# pcb.net
KiCad netlist of a schematic drawn in EAGLE
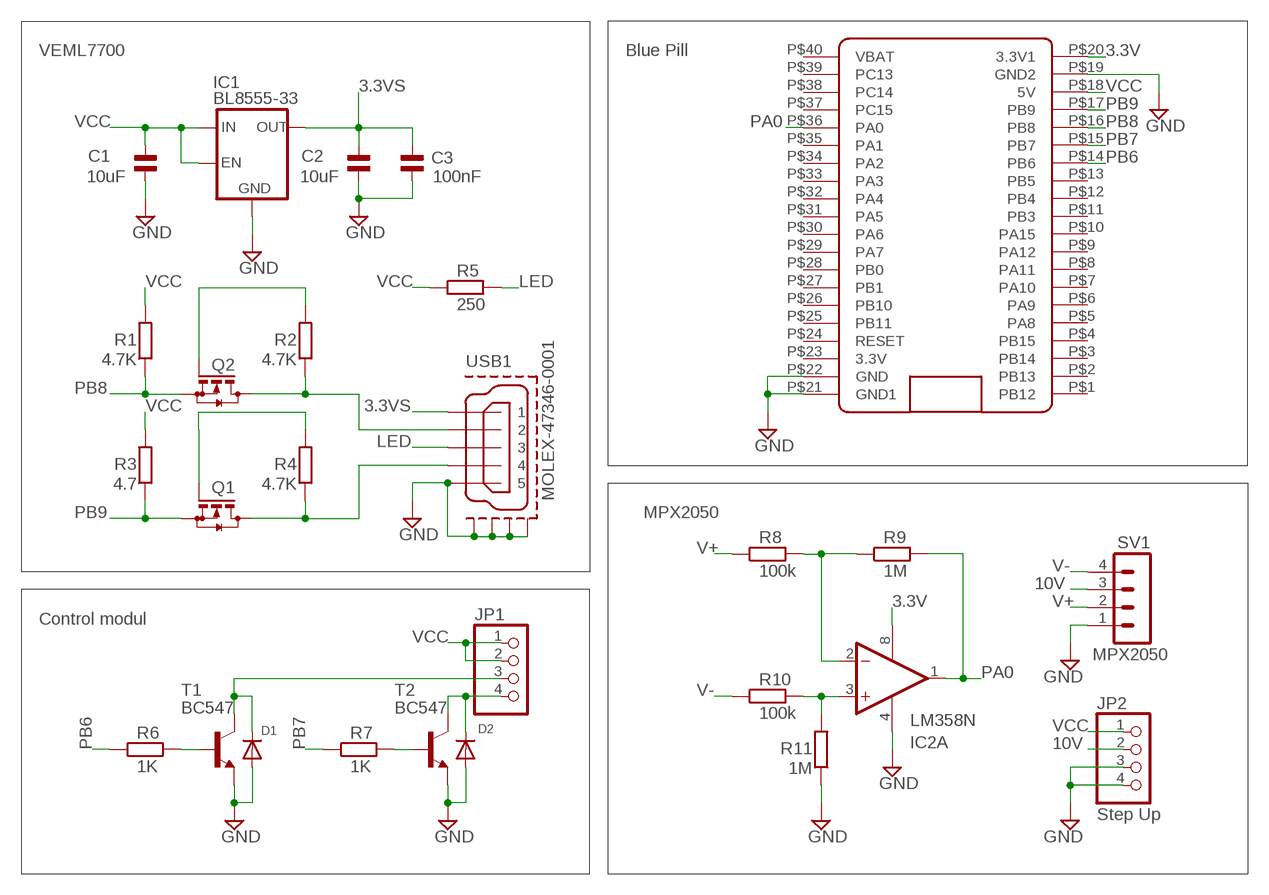
[diagram p0: schematic, sheet 1]

(export (version "E")
  (design (tool "Eeschema 10.0.6"))
  (components
    (comp (ref "C1")
      (value "10uF")
      (footprint "eagle-import:C-0805")
      (libsource (lib "eagle-import") (part "C-NP-SMD-0805"))
    )
    (comp (ref "C2")
      (value "10uF")
      (footprint "eagle-import:C-0805")
      (libsource (lib "eagle-import") (part "C-NP-SMD-0805"))
    )
    (comp (ref "C3")
      (value "100nF")
      (footprint "eagle-import:C-0805")
      (libsource (lib "eagle-import") (part "C-NP-SMD-0805"))
    )
    (comp (ref "D1")
      (value "DIODESOD-123")
      (footprint "eagle-import:SOD-123")
      (libsource (lib "eagle-import") (part "DIODESOD-123"))
    )
    (comp (ref "D2")
      (value "DIODESOD-123")
      (footprint "eagle-import:SOD-123")
      (libsource (lib "eagle-import") (part "DIODESOD-123"))
    )
    (comp (ref "IC1")
      (value "BL8555-33")
      (footprint "eagle-import:SOT23-5")
      (fields (field (name "MF") "Texas Instruments") (field (name "MPN") "TPS70928DBVT"))
      (libsource (lib "eagle-import") (part "TPS709DBV28"))
    )
    (comp (ref "IC2")
      (value "LM358N")
      (footprint "eagle-import:DIL08")
      (libsource (lib "eagle-import") (part "LM358N"))
    )
    (comp (ref "JP1")
      (value "PINHD-1X4")
      (footprint "eagle-import:1X04")
      (libsource (lib "eagle-import") (part "PINHD-1X4"))
    )
    (comp (ref "JP2")
      (value "Step Up")
      (footprint "eagle-import:1X04")
      (libsource (lib "eagle-import") (part "PINHD-1X4"))
    )
    (comp (ref "Q1")
      (value "BSS123")
      (footprint "eagle-import:SOT23")
      (libsource (lib "eagle-import") (part "BSS123"))
    )
    (comp (ref "Q2")
      (value "BSS123")
      (footprint "eagle-import:SOT23")
      (libsource (lib "eagle-import") (part "BSS123"))
    )
    (comp (ref "R1")
      (value "4.7K")
      (footprint "eagle-import:M0805")
      (libsource (lib "eagle-import") (part "resistor_348_R-EU_M0805"))
    )
    (comp (ref "R2")
      (value "4.7K")
      (footprint "eagle-import:M0805")
      (libsource (lib "eagle-import") (part "resistor_348_R-EU_M0805"))
    )
    (comp (ref "R3")
      (value "4.7")
      (footprint "eagle-import:M0805")
      (libsource (lib "eagle-import") (part "resistor_348_R-EU_M0805"))
    )
    (comp (ref "R4")
      (value "4.7K")
      (footprint "eagle-import:M0805")
      (libsource (lib "eagle-import") (part "resistor_348_R-EU_M0805"))
    )
    (comp (ref "R5")
      (value "250")
      (footprint "eagle-import:0204_7")
      (libsource (lib "eagle-import") (part "R-EU_0204/7"))
    )
    (comp (ref "R6")
      (value "1K")
      (footprint "eagle-import:0204_7")
      (libsource (lib "eagle-import") (part "R-EU_0204/7"))
    )
    (comp (ref "R7")
      (value "1K")
      (footprint "eagle-import:0204_7")
      (libsource (lib "eagle-import") (part "R-EU_0204/7"))
    )
    (comp (ref "R8")
      (value "100k")
      (footprint "eagle-import:0204_7")
      (libsource (lib "eagle-import") (part "R-EU_0204/7"))
    )
    (comp (ref "R9")
      (value "1M")
      (footprint "eagle-import:0204_7")
      (libsource (lib "eagle-import") (part "R-EU_0204/7"))
    )
    (comp (ref "R10")
      (value "100k")
      (footprint "eagle-import:0204_7")
      (libsource (lib "eagle-import") (part "R-EU_0204/7"))
    )
    (comp (ref "R11")
      (value "1M")
      (footprint "eagle-import:0204_7")
      (libsource (lib "eagle-import") (part "R-EU_0204/7"))
    )
    (comp (ref "SV1")
      (value "MPX2050")
      (footprint "eagle-import:MA04-1")
      (libsource (lib "eagle-import") (part "MA04-1"))
    )
    (comp (ref "T1")
      (value "BC547")
      (footprint "eagle-import:TO92")
      (libsource (lib "eagle-import") (part "BC547"))
    )
    (comp (ref "T2")
      (value "BC547")
      (footprint "eagle-import:TO92")
      (libsource (lib "eagle-import") (part "BC547"))
    )
    (comp (ref "U$1")
      (value "stm32f103c8t6")
      (footprint "eagle-import:BLUE_PILL")
      (libsource (lib "eagle-import") (part "BLUE_PILL"))
    )
    (comp (ref "USB1")
      (value "MOLEX-47346-0001")
      (footprint "eagle-import:MOLEX-47364-0001")
      (libsource (lib "eagle-import") (part "MOLEX-47346-0001"))
    )
  )
  (nets
    (net (code "1") (name "/3.3V") (class "Default")
      (node (ref "IC2") (pin "8") (pinfunction "V+_8") (pintype "power_in"))
      (node (ref "U$1") (pin "P$20") (pinfunction "3.3V1_P$20") (pintype "bidirectional"))
    )
    (net (code "2") (name "/3.3VS") (class "Default")
      (node (ref "C2") (pin "2") (pinfunction "2_2") (pintype "passive"))
      (node (ref "C3") (pin "2") (pinfunction "2_2") (pintype "passive"))
      (node (ref "IC1") (pin "5") (pinfunction "OUT_5") (pintype "passive"))
      (node (ref "USB1") (pin "1") (pinfunction "1_1") (pintype "input"))
    )
    (net (code "3") (name "/10V") (class "Default")
      (node (ref "JP2") (pin "2") (pinfunction "2_2") (pintype "passive"))
      (node (ref "SV1") (pin "3") (pinfunction "3_3") (pintype "passive"))
    )
    (net (code "4") (name "/LED") (class "Default")
      (node (ref "R5") (pin "2") (pinfunction "2_2") (pintype "passive"))
      (node (ref "USB1") (pin "3") (pinfunction "3_3") (pintype "input"))
    )
    (net (code "5") (name "/PA0") (class "Default")
      (node (ref "IC2") (pin "1") (pinfunction "OUT_1") (pintype "output"))
      (node (ref "R9") (pin "2") (pinfunction "2_2") (pintype "passive"))
      (node (ref "U$1") (pin "P$36") (pinfunction "PA0_P$36") (pintype "bidirectional"))
    )
    (net (code "6") (name "/PB6") (class "Default")
      (node (ref "R6") (pin "1") (pinfunction "1_1") (pintype "passive"))
      (node (ref "U$1") (pin "P$14") (pinfunction "PB6_P$14") (pintype "bidirectional"))
    )
    (net (code "7") (name "/PB7") (class "Default")
      (node (ref "R7") (pin "1") (pinfunction "1_1") (pintype "passive"))
      (node (ref "U$1") (pin "P$15") (pinfunction "PB7_P$15") (pintype "bidirectional"))
    )
    (net (code "8") (name "/PB8") (class "Default")
      (node (ref "Q2") (pin "2") (pinfunction "S_2") (pintype "passive"))
      (node (ref "R1") (pin "1") (pinfunction "1_1") (pintype "passive"))
      (node (ref "U$1") (pin "P$16") (pinfunction "PB8_P$16") (pintype "bidirectional"))
    )
    (net (code "9") (name "/PB9") (class "Default")
      (node (ref "Q1") (pin "2") (pinfunction "S_2") (pintype "passive"))
      (node (ref "R3") (pin "1") (pinfunction "1_1") (pintype "passive"))
      (node (ref "U$1") (pin "P$17") (pinfunction "PB9_P$17") (pintype "bidirectional"))
    )
    (net (code "10") (name "/V+") (class "Default")
      (node (ref "R8") (pin "1") (pinfunction "1_1") (pintype "passive"))
      (node (ref "SV1") (pin "2") (pinfunction "2_2") (pintype "passive"))
    )
    (net (code "11") (name "/V-") (class "Default")
      (node (ref "R10") (pin "1") (pinfunction "1_1") (pintype "passive"))
      (node (ref "SV1") (pin "4") (pinfunction "4_4") (pintype "passive"))
    )
    (net (code "12") (name "/VCC") (class "Default")
      (node (ref "C1") (pin "2") (pinfunction "2_2") (pintype "passive"))
      (node (ref "IC1") (pin "1") (pinfunction "IN_1") (pintype "input"))
      (node (ref "IC1") (pin "3") (pinfunction "EN_3") (pintype "input"))
      (node (ref "JP1") (pin "1") (pinfunction "1_1") (pintype "passive"))
      (node (ref "JP1") (pin "2") (pinfunction "2_2") (pintype "passive"))
      (node (ref "JP2") (pin "1") (pinfunction "1_1") (pintype "passive"))
      (node (ref "R1") (pin "2") (pinfunction "2_2") (pintype "passive"))
      (node (ref "R3") (pin "2") (pinfunction "2_2") (pintype "passive"))
      (node (ref "R5") (pin "1") (pinfunction "1_1") (pintype "passive"))
      (node (ref "U$1") (pin "P$18") (pinfunction "5V_P$18") (pintype "bidirectional"))
    )
    (net (code "13") (name "GND") (class "Default")
      (node (ref "C1") (pin "1") (pinfunction "1_1") (pintype "passive"))
      (node (ref "C2") (pin "1") (pinfunction "1_1") (pintype "passive"))
      (node (ref "C3") (pin "1") (pinfunction "1_1") (pintype "passive"))
      (node (ref "D1") (pin "A") (pinfunction "A_A") (pintype "passive"))
      (node (ref "D2") (pin "A") (pinfunction "A_A") (pintype "passive"))
      (node (ref "IC1") (pin "2") (pinfunction "GND_2") (pintype "input"))
      (node (ref "IC2") (pin "4") (pinfunction "V-_4") (pintype "power_in"))
      (node (ref "JP2") (pin "3") (pinfunction "3_3") (pintype "passive"))
      (node (ref "JP2") (pin "4") (pinfunction "4_4") (pintype "passive"))
      (node (ref "R11") (pin "1") (pinfunction "1_1") (pintype "passive"))
      (node (ref "SV1") (pin "1") (pinfunction "1_1") (pintype "passive"))
      (node (ref "T1") (pin "1") (pinfunction "E_1") (pintype "passive"))
      (node (ref "T2") (pin "1") (pinfunction "E_1") (pintype "passive"))
      (node (ref "U$1") (pin "P$19") (pinfunction "GND2_P$19") (pintype "bidirectional"))
      (node (ref "U$1") (pin "P$21") (pinfunction "GND1_P$21") (pintype "power_in"))
      (node (ref "U$1") (pin "P$22") (pinfunction "GND_P$22") (pintype "bidirectional"))
      (node (ref "USB1") (pin "5") (pinfunction "5_5") (pintype "input"))
      (node (ref "USB1") (pin "GND1") (pinfunction "GND1_GND1") (pintype "bidirectional"))
      (node (ref "USB1") (pin "GND2") (pinfunction "GND2_GND2") (pintype "bidirectional"))
      (node (ref "USB1") (pin "GND3") (pinfunction "GND3_GND3") (pintype "bidirectional"))
      (node (ref "USB1") (pin "GND4") (pinfunction "GND4_GND4") (pintype "bidirectional"))
    )
    (net (code "14") (name "Net-(IC2A-+IN)") (class "Default")
      (node (ref "IC2") (pin "3") (pinfunction "+IN_3") (pintype "input"))
      (node (ref "R10") (pin "2") (pinfunction "2_2") (pintype "passive"))
      (node (ref "R11") (pin "2") (pinfunction "2_2") (pintype "passive"))
    )
    (net (code "15") (name "Net-(IC2A--IN)") (class "Default")
      (node (ref "IC2") (pin "2") (pinfunction "-IN_2") (pintype "input"))
      (node (ref "R8") (pin "2") (pinfunction "2_2") (pintype "passive"))
      (node (ref "R9") (pin "1") (pinfunction "1_1") (pintype "passive"))
    )
    (net (code "16") (name "Net-(Q1-D)") (class "Default")
      (node (ref "Q1") (pin "3") (pinfunction "D_3") (pintype "passive"))
      (node (ref "R4") (pin "1") (pinfunction "1_1") (pintype "passive"))
      (node (ref "USB1") (pin "4") (pinfunction "4_4") (pintype "input"))
    )
    (net (code "17") (name "Net-(Q1-G)") (class "Default")
      (node (ref "Q1") (pin "1") (pinfunction "G_1") (pintype "passive"))
      (node (ref "R4") (pin "2") (pinfunction "2_2") (pintype "passive"))
    )
    (net (code "18") (name "Net-(Q2-D)") (class "Default")
      (node (ref "Q2") (pin "3") (pinfunction "D_3") (pintype "passive"))
      (node (ref "R2") (pin "1") (pinfunction "1_1") (pintype "passive"))
      (node (ref "USB1") (pin "2") (pinfunction "2_2") (pintype "input"))
    )
    (net (code "19") (name "Net-(Q2-G)") (class "Default")
      (node (ref "Q2") (pin "1") (pinfunction "G_1") (pintype "passive"))
      (node (ref "R2") (pin "2") (pinfunction "2_2") (pintype "passive"))
    )
    (net (code "20") (name "Net-(T1-B)") (class "Default")
      (node (ref "R6") (pin "2") (pinfunction "2_2") (pintype "passive"))
      (node (ref "T1") (pin "2") (pinfunction "B_2") (pintype "passive"))
    )
    (net (code "21") (name "Net-(T1-C)") (class "Default")
      (node (ref "D1") (pin "C") (pinfunction "C_C") (pintype "passive"))
      (node (ref "JP1") (pin "3") (pinfunction "3_3") (pintype "passive"))
      (node (ref "T1") (pin "3") (pinfunction "C_3") (pintype "passive"))
    )
    (net (code "22") (name "Net-(T2-B)") (class "Default")
      (node (ref "R7") (pin "2") (pinfunction "2_2") (pintype "passive"))
      (node (ref "T2") (pin "2") (pinfunction "B_2") (pintype "passive"))
    )
    (net (code "23") (name "Net-(T2-C)") (class "Default")
      (node (ref "D2") (pin "C") (pinfunction "C_C") (pintype "passive"))
      (node (ref "JP1") (pin "4") (pinfunction "4_4") (pintype "passive"))
      (node (ref "T2") (pin "3") (pinfunction "C_3") (pintype "passive"))
    )
    (net (code "24") (name "unconnected-(U$1-3.3V-PadP$23)") (class "Default")
      (node (ref "U$1") (pin "P$23") (pinfunction "3.3V_P$23") (pintype "bidirectional"))
    )
    (net (code "25") (name "unconnected-(U$1-PA1-PadP$35)") (class "Default")
      (node (ref "U$1") (pin "P$35") (pinfunction "PA1_P$35") (pintype "bidirectional"))
    )
    (net (code "26") (name "unconnected-(U$1-PA2-PadP$34)") (class "Default")
      (node (ref "U$1") (pin "P$34") (pinfunction "PA2_P$34") (pintype "bidirectional"))
    )
    (net (code "27") (name "unconnected-(U$1-PA3-PadP$33)") (class "Default")
      (node (ref "U$1") (pin "P$33") (pinfunction "PA3_P$33") (pintype "bidirectional"))
    )
    (net (code "28") (name "unconnected-(U$1-PA4-PadP$32)") (class "Default")
      (node (ref "U$1") (pin "P$32") (pinfunction "PA4_P$32") (pintype "bidirectional"))
    )
    (net (code "29") (name "unconnected-(U$1-PA5-PadP$31)") (class "Default")
      (node (ref "U$1") (pin "P$31") (pinfunction "PA5_P$31") (pintype "bidirectional"))
    )
    (net (code "30") (name "unconnected-(U$1-PA6-PadP$30)") (class "Default")
      (node (ref "U$1") (pin "P$30") (pinfunction "PA6_P$30") (pintype "bidirectional"))
    )
    (net (code "31") (name "unconnected-(U$1-PA7-PadP$29)") (class "Default")
      (node (ref "U$1") (pin "P$29") (pinfunction "PA7_P$29") (pintype "bidirectional"))
    )
    (net (code "32") (name "unconnected-(U$1-PA8-PadP$5)") (class "Default")
      (node (ref "U$1") (pin "P$5") (pinfunction "PA8_P$5") (pintype "bidirectional"))
    )
    (net (code "33") (name "unconnected-(U$1-PA9-PadP$6)") (class "Default")
      (node (ref "U$1") (pin "P$6") (pinfunction "PA9_P$6") (pintype "bidirectional"))
    )
    (net (code "34") (name "unconnected-(U$1-PA10-PadP$7)") (class "Default")
      (node (ref "U$1") (pin "P$7") (pinfunction "PA10_P$7") (pintype "bidirectional"))
    )
    (net (code "35") (name "unconnected-(U$1-PA11-PadP$8)") (class "Default")
      (node (ref "U$1") (pin "P$8") (pinfunction "PA11_P$8") (pintype "bidirectional"))
    )
    (net (code "36") (name "unconnected-(U$1-PA12-PadP$9)") (class "Default")
      (node (ref "U$1") (pin "P$9") (pinfunction "PA12_P$9") (pintype "bidirectional"))
    )
    (net (code "37") (name "unconnected-(U$1-PA15-PadP$10)") (class "Default")
      (node (ref "U$1") (pin "P$10") (pinfunction "PA15_P$10") (pintype "bidirectional"))
    )
    (net (code "38") (name "unconnected-(U$1-PB0-PadP$28)") (class "Default")
      (node (ref "U$1") (pin "P$28") (pinfunction "PB0_P$28") (pintype "bidirectional"))
    )
    (net (code "39") (name "unconnected-(U$1-PB1-PadP$27)") (class "Default")
      (node (ref "U$1") (pin "P$27") (pinfunction "PB1_P$27") (pintype "bidirectional"))
    )
    (net (code "40") (name "unconnected-(U$1-PB3-PadP$11)") (class "Default")
      (node (ref "U$1") (pin "P$11") (pinfunction "PB3_P$11") (pintype "bidirectional"))
    )
    (net (code "41") (name "unconnected-(U$1-PB4-PadP$12)") (class "Default")
      (node (ref "U$1") (pin "P$12") (pinfunction "PB4_P$12") (pintype "bidirectional"))
    )
    (net (code "42") (name "unconnected-(U$1-PB5-PadP$13)") (class "Default")
      (node (ref "U$1") (pin "P$13") (pinfunction "PB5_P$13") (pintype "bidirectional"))
    )
    (net (code "43") (name "unconnected-(U$1-PB10-PadP$26)") (class "Default")
      (node (ref "U$1") (pin "P$26") (pinfunction "PB10_P$26") (pintype "bidirectional"))
    )
    (net (code "44") (name "unconnected-(U$1-PB11-PadP$25)") (class "Default")
      (node (ref "U$1") (pin "P$25") (pinfunction "PB11_P$25") (pintype "bidirectional"))
    )
    (net (code "45") (name "unconnected-(U$1-PB12-PadP$1)") (class "Default")
      (node (ref "U$1") (pin "P$1") (pinfunction "PB12_P$1") (pintype "bidirectional"))
    )
    (net (code "46") (name "unconnected-(U$1-PB13-PadP$2)") (class "Default")
      (node (ref "U$1") (pin "P$2") (pinfunction "PB13_P$2") (pintype "bidirectional"))
    )
    (net (code "47") (name "unconnected-(U$1-PB14-PadP$3)") (class "Default")
      (node (ref "U$1") (pin "P$3") (pinfunction "PB14_P$3") (pintype "bidirectional"))
    )
    (net (code "48") (name "unconnected-(U$1-PB15-PadP$4)") (class "Default")
      (node (ref "U$1") (pin "P$4") (pinfunction "PB15_P$4") (pintype "bidirectional"))
    )
    (net (code "49") (name "unconnected-(U$1-PC13-PadP$39)") (class "Default")
      (node (ref "U$1") (pin "P$39") (pinfunction "PC13_P$39") (pintype "bidirectional"))
    )
    (net (code "50") (name "unconnected-(U$1-PC14-PadP$38)") (class "Default")
      (node (ref "U$1") (pin "P$38") (pinfunction "PC14_P$38") (pintype "bidirectional"))
    )
    (net (code "51") (name "unconnected-(U$1-PC15-PadP$37)") (class "Default")
      (node (ref "U$1") (pin "P$37") (pinfunction "PC15_P$37") (pintype "bidirectional"))
    )
    (net (code "52") (name "unconnected-(U$1-RESET-PadP$24)") (class "Default")
      (node (ref "U$1") (pin "P$24") (pinfunction "RESET_P$24") (pintype "bidirectional"))
    )
    (net (code "53") (name "unconnected-(U$1-VBAT-PadP$40)") (class "Default")
      (node (ref "U$1") (pin "P$40") (pinfunction "VBAT_P$40") (pintype "bidirectional"))
    )
  )
)
